# Smarttree_CMU_5_2_3.net
KiCad netlist of a schematic drawn in EAGLE
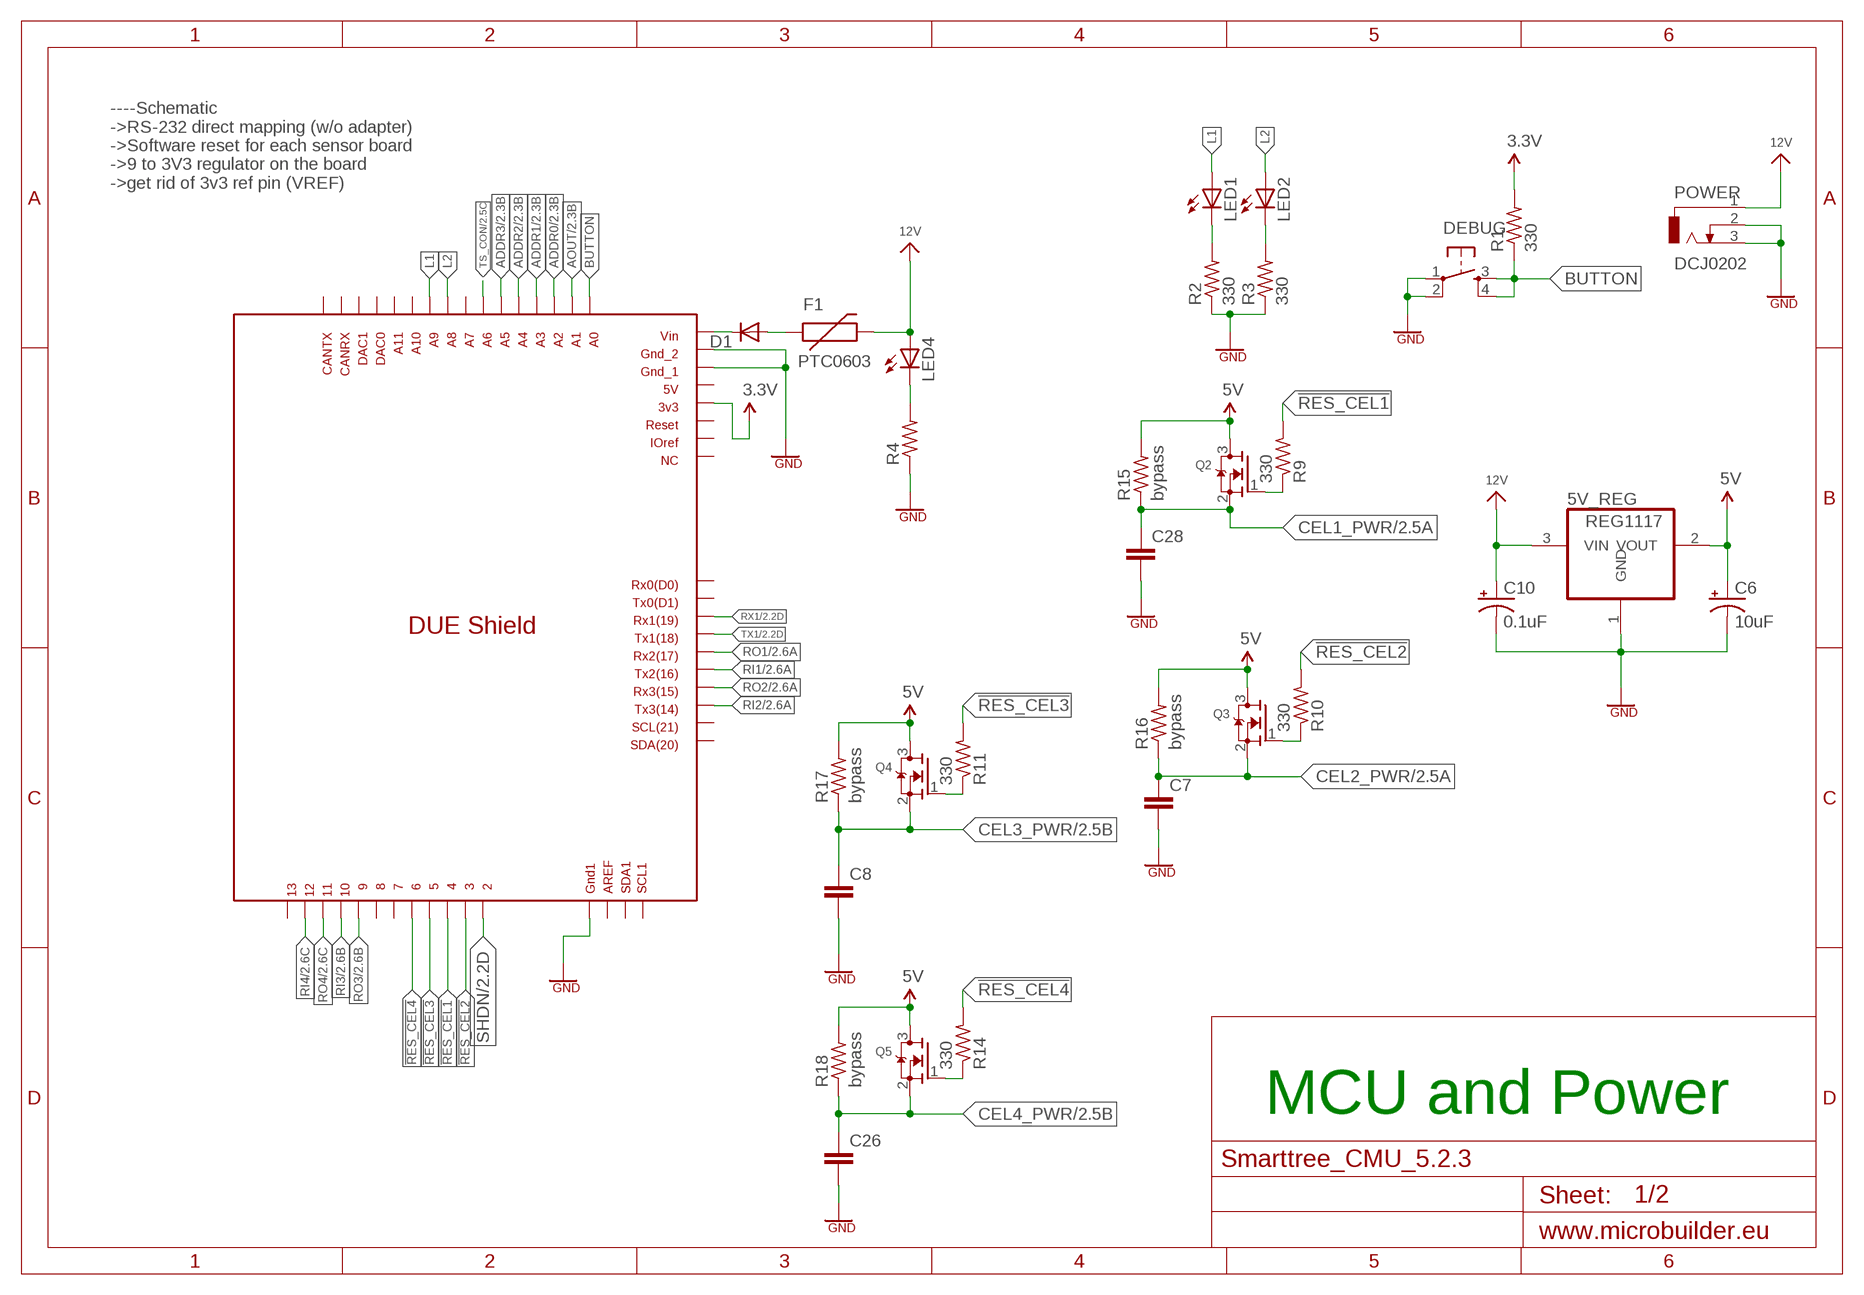
[diagram p0: schematic, sheet 1]
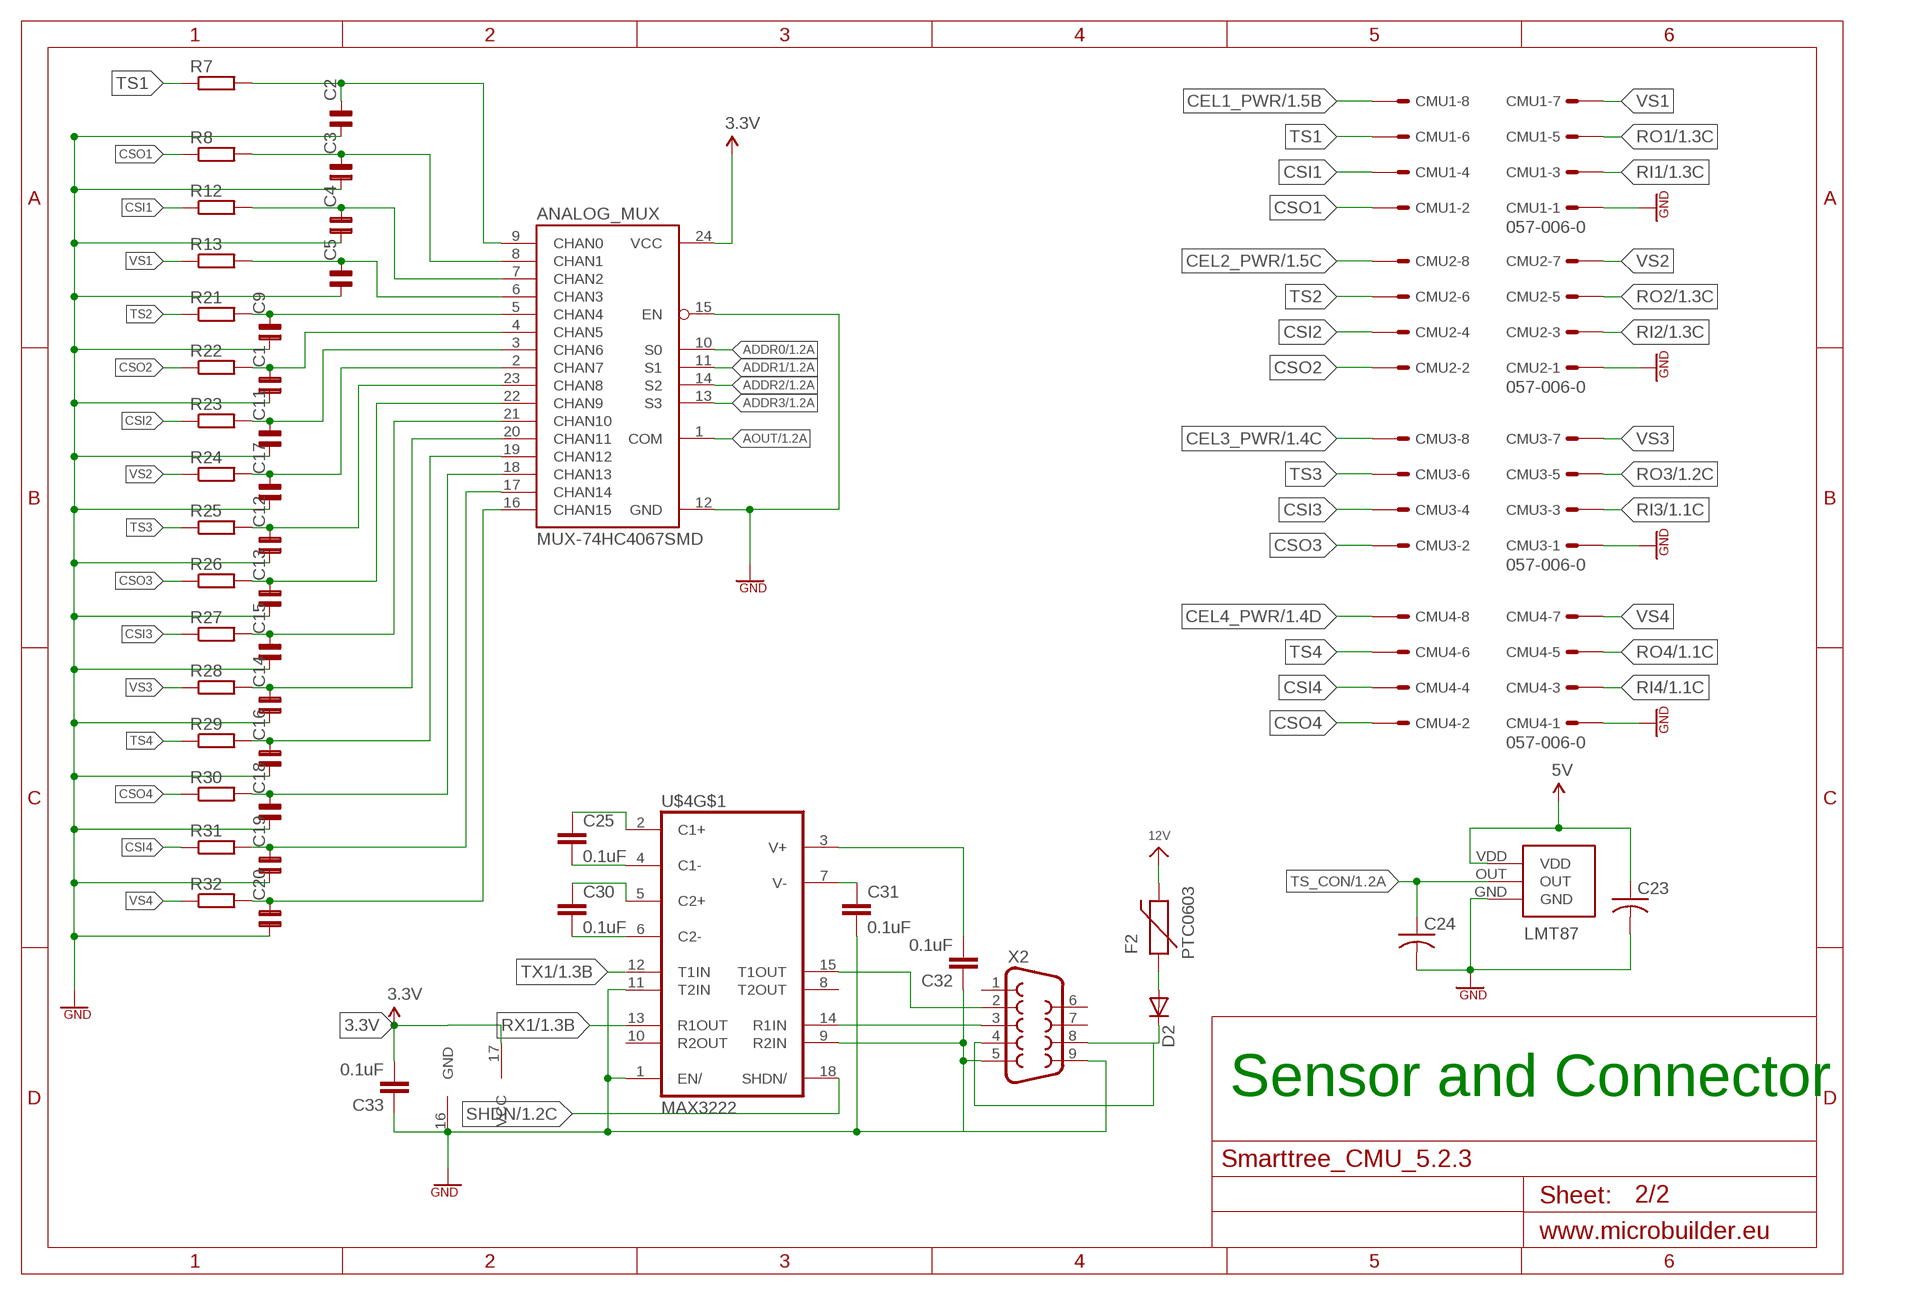
[diagram p1: schematic, sheet 2]

(export (version "E")
  (design (tool "Eeschema 10.0.6"))
  (components
    (comp (ref "ANALOG_MUX")
      (value "MUX-74HC4067SMD")
      (footprint "eagle-import:SSOP24")
      (libsource (lib "eagle-import") (part "MUX-74HC4067SMD"))
    )
    (comp (ref "C1")
      (value "C-NP-SMD-0805")
      (footprint "eagle-import:C-0805")
      (libsource (lib "eagle-import") (part "C-NP-SMD-0805"))
    )
    (comp (ref "C2")
      (value "C-NP-SMD-0805")
      (footprint "eagle-import:C-0805")
      (libsource (lib "eagle-import") (part "C-NP-SMD-0805"))
    )
    (comp (ref "C3")
      (value "C-NP-SMD-0805")
      (footprint "eagle-import:C-0805")
      (libsource (lib "eagle-import") (part "C-NP-SMD-0805"))
    )
    (comp (ref "C4")
      (value "C-NP-SMD-0805")
      (footprint "eagle-import:C-0805")
      (libsource (lib "eagle-import") (part "C-NP-SMD-0805"))
    )
    (comp (ref "C5")
      (value "C-NP-SMD-0805")
      (footprint "eagle-import:C-0805")
      (libsource (lib "eagle-import") (part "C-NP-SMD-0805"))
    )
    (comp (ref "C9")
      (value "C-NP-SMD-0805")
      (footprint "eagle-import:C-0805")
      (libsource (lib "eagle-import") (part "C-NP-SMD-0805"))
    )
    (comp (ref "C11")
      (value "C-NP-SMD-0805")
      (footprint "eagle-import:C-0805")
      (libsource (lib "eagle-import") (part "C-NP-SMD-0805"))
    )
    (comp (ref "C12")
      (value "C-NP-SMD-0805")
      (footprint "eagle-import:C-0805")
      (libsource (lib "eagle-import") (part "C-NP-SMD-0805"))
    )
    (comp (ref "C13")
      (value "C-NP-SMD-0805")
      (footprint "eagle-import:C-0805")
      (libsource (lib "eagle-import") (part "C-NP-SMD-0805"))
    )
    (comp (ref "C14")
      (value "C-NP-SMD-0805")
      (footprint "eagle-import:C-0805")
      (libsource (lib "eagle-import") (part "C-NP-SMD-0805"))
    )
    (comp (ref "C15")
      (value "C-NP-SMD-0805")
      (footprint "eagle-import:C-0805")
      (libsource (lib "eagle-import") (part "C-NP-SMD-0805"))
    )
    (comp (ref "C16")
      (value "C-NP-SMD-0805")
      (footprint "eagle-import:C-0805")
      (libsource (lib "eagle-import") (part "C-NP-SMD-0805"))
    )
    (comp (ref "C17")
      (value "C-NP-SMD-0805")
      (footprint "eagle-import:C-0805")
      (libsource (lib "eagle-import") (part "C-NP-SMD-0805"))
    )
    (comp (ref "C18")
      (value "C-NP-SMD-0805")
      (footprint "eagle-import:C-0805")
      (libsource (lib "eagle-import") (part "C-NP-SMD-0805"))
    )
    (comp (ref "C19")
      (value "C-NP-SMD-0805")
      (footprint "eagle-import:C-0805")
      (libsource (lib "eagle-import") (part "C-NP-SMD-0805"))
    )
    (comp (ref "C20")
      (value "C-NP-SMD-0805")
      (footprint "eagle-import:C-0805")
      (libsource (lib "eagle-import") (part "C-NP-SMD-0805"))
    )
    (comp (ref "C23")
      (value "C-USC0805")
      (footprint "eagle-import:C0805")
      (libsource (lib "eagle-import") (part "C-USC0805"))
    )
    (comp (ref "C24")
      (value "C-USC0805")
      (footprint "eagle-import:C0805")
      (libsource (lib "eagle-import") (part "C-USC0805"))
    )
    (comp (ref "C25")
      (value "0.1uF")
      (footprint "eagle-import:0603-CAP")
      (libsource (lib "eagle-import") (part "CAP0603-CAP"))
    )
    (comp (ref "C30")
      (value "0.1uF")
      (footprint "eagle-import:0603-CAP")
      (libsource (lib "eagle-import") (part "CAP0603-CAP"))
    )
    (comp (ref "C31")
      (value "0.1uF")
      (footprint "eagle-import:0603-CAP")
      (libsource (lib "eagle-import") (part "CAP0603-CAP"))
    )
    (comp (ref "C32")
      (value "0.1uF")
      (footprint "eagle-import:0603-CAP")
      (libsource (lib "eagle-import") (part "CAP0603-CAP"))
    )
    (comp (ref "C33")
      (value "0.1uF")
      (footprint "eagle-import:0603-CAP")
      (libsource (lib "eagle-import") (part "CAP0603-CAP"))
    )
    (comp (ref "CMU1")
      (value "057-006-0")
      (footprint "eagle-import:057-006-0")
      (libsource (lib "eagle-import") (part "057-006-0"))
    )
    (comp (ref "CMU2")
      (value "057-006-0")
      (footprint "eagle-import:057-006-0")
      (libsource (lib "eagle-import") (part "057-006-0"))
    )
    (comp (ref "CMU3")
      (value "057-006-0")
      (footprint "eagle-import:057-006-0")
      (libsource (lib "eagle-import") (part "057-006-0"))
    )
    (comp (ref "CMU4")
      (value "057-006-0")
      (footprint "eagle-import:057-006-0")
      (libsource (lib "eagle-import") (part "057-006-0"))
    )
    (comp (ref "D2")
      (value "DIODE-SOD106-R")
      (footprint "eagle-import:SOD106-R")
      (libsource (lib "eagle-import") (part "DIODE-SOD106-R"))
    )
    (comp (ref "F2")
      (value "PTC0603")
      (footprint "eagle-import:0603")
      (libsource (lib "eagle-import") (part "PTC0603"))
    )
    (comp (ref "LMT87")
      (value "LMT87_PAC")
      (footprint "eagle-import:LMT87_TO")
      (libsource (lib "eagle-import") (part "LMT87_PAC"))
    )
    (comp (ref "R7")
      (value "R-EU_R0805W")
      (footprint "eagle-import:R0805W")
      (libsource (lib "eagle-import") (part "R-EU_R0805W"))
    )
    (comp (ref "R8")
      (value "R-EU_R0805W")
      (footprint "eagle-import:R0805W")
      (libsource (lib "eagle-import") (part "R-EU_R0805W"))
    )
    (comp (ref "R12")
      (value "R-EU_R0805W")
      (footprint "eagle-import:R0805W")
      (libsource (lib "eagle-import") (part "R-EU_R0805W"))
    )
    (comp (ref "R13")
      (value "R-EU_R0805W")
      (footprint "eagle-import:R0805W")
      (libsource (lib "eagle-import") (part "R-EU_R0805W"))
    )
    (comp (ref "R21")
      (value "R-EU_R0805W")
      (footprint "eagle-import:R0805W")
      (libsource (lib "eagle-import") (part "R-EU_R0805W"))
    )
    (comp (ref "R22")
      (value "R-EU_R0805W")
      (footprint "eagle-import:R0805W")
      (libsource (lib "eagle-import") (part "R-EU_R0805W"))
    )
    (comp (ref "R23")
      (value "R-EU_R0805W")
      (footprint "eagle-import:R0805W")
      (libsource (lib "eagle-import") (part "R-EU_R0805W"))
    )
    (comp (ref "R24")
      (value "R-EU_R0805W")
      (footprint "eagle-import:R0805W")
      (libsource (lib "eagle-import") (part "R-EU_R0805W"))
    )
    (comp (ref "R25")
      (value "R-EU_R0805W")
      (footprint "eagle-import:R0805W")
      (libsource (lib "eagle-import") (part "R-EU_R0805W"))
    )
    (comp (ref "R26")
      (value "R-EU_R0805W")
      (footprint "eagle-import:R0805W")
      (libsource (lib "eagle-import") (part "R-EU_R0805W"))
    )
    (comp (ref "R27")
      (value "R-EU_R0805W")
      (footprint "eagle-import:R0805W")
      (libsource (lib "eagle-import") (part "R-EU_R0805W"))
    )
    (comp (ref "R28")
      (value "R-EU_R0805W")
      (footprint "eagle-import:R0805W")
      (libsource (lib "eagle-import") (part "R-EU_R0805W"))
    )
    (comp (ref "R29")
      (value "R-EU_R0805W")
      (footprint "eagle-import:R0805W")
      (libsource (lib "eagle-import") (part "R-EU_R0805W"))
    )
    (comp (ref "R30")
      (value "R-EU_R0805W")
      (footprint "eagle-import:R0805W")
      (libsource (lib "eagle-import") (part "R-EU_R0805W"))
    )
    (comp (ref "R31")
      (value "R-EU_R0805W")
      (footprint "eagle-import:R0805W")
      (libsource (lib "eagle-import") (part "R-EU_R0805W"))
    )
    (comp (ref "R32")
      (value "R-EU_R0805W")
      (footprint "eagle-import:R0805W")
      (libsource (lib "eagle-import") (part "R-EU_R0805W"))
    )
    (comp (ref "U$4")
      (value "MAX3222")
      (footprint "eagle-import:SO18")
      (libsource (lib "eagle-import") (part "MAX3222"))
    )
    (comp (ref "X2")
      (value "DB9MALE")
      (footprint "eagle-import:DB9_MALE")
      (libsource (lib "eagle-import") (part "DB9MALE"))
    )
    (comp (ref "5V_REG")
      (value "REG1117")
      (footprint "eagle-import:SOT223")
      (libsource (lib "eagle-import") (part "REG1117"))
    )
    (comp (ref "C6")
      (value "10uF")
      (footprint "eagle-import:EIA3216")
      (libsource (lib "eagle-import") (part "10UF-TANT"))
    )
    (comp (ref "C7")
      (value "CAP0603-CAP")
      (footprint "eagle-import:0603-CAP")
      (libsource (lib "eagle-import") (part "CAP0603-CAP"))
    )
    (comp (ref "C8")
      (value "CAP0603-CAP")
      (footprint "eagle-import:0603-CAP")
      (libsource (lib "eagle-import") (part "CAP0603-CAP"))
    )
    (comp (ref "C10")
      (value "0.1uF")
      (footprint "eagle-import:EIA3216")
      (libsource (lib "eagle-import") (part "10UF-TANT"))
    )
    (comp (ref "C26")
      (value "CAP0603-CAP")
      (footprint "eagle-import:0603-CAP")
      (libsource (lib "eagle-import") (part "CAP0603-CAP"))
    )
    (comp (ref "C28")
      (value "CAP0603-CAP")
      (footprint "eagle-import:0603-CAP")
      (libsource (lib "eagle-import") (part "CAP0603-CAP"))
    )
    (comp (ref "D1")
      (value "DIODE-SOD106-R")
      (footprint "eagle-import:SOD106-R")
      (libsource (lib "eagle-import") (part "DIODE-SOD106-R"))
    )
    (comp (ref "DEBUG")
      (value "TAC_SWITCHSMD")
      (footprint "eagle-import:TACTILE_SWITCH_SMD")
      (libsource (lib "eagle-import") (part "TAC_SWITCHSMD"))
    )
    (comp (ref "F1")
      (value "PTC0603")
      (footprint "eagle-import:0603")
      (libsource (lib "eagle-import") (part "PTC0603"))
    )
    (comp (ref "LED1")
      (value "LED-YELLOW0603")
      (footprint "eagle-import:LED-0603")
      (libsource (lib "eagle-import") (part "LED-YELLOW0603"))
    )
    (comp (ref "LED2")
      (value "LED-YELLOW0603")
      (footprint "eagle-import:LED-0603")
      (libsource (lib "eagle-import") (part "LED-YELLOW0603"))
    )
    (comp (ref "LED4")
      (value "LED-YELLOW0603")
      (footprint "eagle-import:LED-0603")
      (libsource (lib "eagle-import") (part "LED-YELLOW0603"))
    )
    (comp (ref "POWER")
      (value "DCJ0202")
      (footprint "eagle-import:DCJ0202")
      (libsource (lib "eagle-import") (part "DCJ0202"))
    )
    (comp (ref "Q2")
      (value "MOSFET-NREFLOW")
      (footprint "eagle-import:SOT23")
      (libsource (lib "eagle-import") (part "MOSFET-NREFLOW"))
    )
    (comp (ref "Q3")
      (value "MOSFET-NREFLOW")
      (footprint "eagle-import:SOT23")
      (libsource (lib "eagle-import") (part "MOSFET-NREFLOW"))
    )
    (comp (ref "Q4")
      (value "MOSFET-NREFLOW")
      (footprint "eagle-import:SOT23")
      (libsource (lib "eagle-import") (part "MOSFET-NREFLOW"))
    )
    (comp (ref "Q5")
      (value "MOSFET-NREFLOW")
      (footprint "eagle-import:SOT23")
      (libsource (lib "eagle-import") (part "MOSFET-NREFLOW"))
    )
    (comp (ref "R1")
      (value "330")
      (footprint "eagle-import:M0805")
      (libsource (lib "eagle-import") (part "R-US_M0805"))
    )
    (comp (ref "R2")
      (value "330")
      (footprint "eagle-import:M0805")
      (libsource (lib "eagle-import") (part "R-US_M0805"))
    )
    (comp (ref "R3")
      (value "330")
      (footprint "eagle-import:M0805")
      (libsource (lib "eagle-import") (part "R-US_M0805"))
    )
    (comp (ref "R4")
      (value "R-US_M0805")
      (footprint "eagle-import:M0805")
      (libsource (lib "eagle-import") (part "R-US_M0805"))
    )
    (comp (ref "R9")
      (value "330")
      (footprint "eagle-import:R0805")
      (libsource (lib "eagle-import") (part "R-US_R0805"))
    )
    (comp (ref "R10")
      (value "330")
      (footprint "eagle-import:R0805")
      (libsource (lib "eagle-import") (part "R-US_R0805"))
    )
    (comp (ref "R11")
      (value "330")
      (footprint "eagle-import:R0805")
      (libsource (lib "eagle-import") (part "R-US_R0805"))
    )
    (comp (ref "R14")
      (value "330")
      (footprint "eagle-import:R0805")
      (libsource (lib "eagle-import") (part "R-US_R0805"))
    )
    (comp (ref "R15")
      (value "bypass")
      (footprint "eagle-import:M0805")
      (libsource (lib "eagle-import") (part "R-US_M0805"))
    )
    (comp (ref "R16")
      (value "bypass")
      (footprint "eagle-import:M0805")
      (libsource (lib "eagle-import") (part "R-US_M0805"))
    )
    (comp (ref "R17")
      (value "bypass")
      (footprint "eagle-import:M0805")
      (libsource (lib "eagle-import") (part "R-US_M0805"))
    )
    (comp (ref "R18")
      (value "bypass")
      (footprint "eagle-import:M0805")
      (libsource (lib "eagle-import") (part "R-US_M0805"))
    )
    (comp (ref "U$1")
      (value "DUE(OUTLINE)")
      (footprint "eagle-import:DUE(NORMAL)")
      (libsource (lib "eagle-import") (part "DUE(OUTLINE)"))
    )
  )
  (nets
    (net (code "1") (name "3.3V") (class "Default")
      (node (ref "ANALOG_MUX") (pin "24") (pinfunction "VCC_24") (pintype "bidirectional"))
      (node (ref "C33") (pin "2") (pinfunction "2_2") (pintype "passive"))
      (node (ref "R1") (pin "2") (pinfunction "2_2") (pintype "passive"))
      (node (ref "U$1") (pin "3V3") (pinfunction "3V3_3V3") (pintype "bidirectional"))
      (node (ref "U$4") (pin "17") (pinfunction "VCC_17") (pintype "bidirectional"))
    )
    (net (code "2") (name "5V") (class "Default")
      (node (ref "5V_REG") (pin "2") (pinfunction "VOUT_2") (pintype "output"))
      (node (ref "C23") (pin "1") (pinfunction "1_1") (pintype "passive"))
      (node (ref "C6") (pin "A") (pinfunction "+_A") (pintype "passive"))
      (node (ref "LMT87") (pin "VDD") (pinfunction "VDD_VDD") (pintype "bidirectional"))
      (node (ref "Q2") (pin "3") (pinfunction "D_3") (pintype "bidirectional"))
      (node (ref "Q3") (pin "3") (pinfunction "D_3") (pintype "bidirectional"))
      (node (ref "Q4") (pin "3") (pinfunction "D_3") (pintype "bidirectional"))
      (node (ref "Q5") (pin "3") (pinfunction "D_3") (pintype "bidirectional"))
      (node (ref "R15") (pin "2") (pinfunction "2_2") (pintype "passive"))
      (node (ref "R16") (pin "2") (pinfunction "2_2") (pintype "passive"))
      (node (ref "R17") (pin "2") (pinfunction "2_2") (pintype "passive"))
      (node (ref "R18") (pin "2") (pinfunction "2_2") (pintype "passive"))
    )
    (net (code "3") (name "12V") (class "Default")
      (node (ref "5V_REG") (pin "3") (pinfunction "VIN_3") (pintype "input"))
      (node (ref "C10") (pin "A") (pinfunction "+_A") (pintype "passive"))
      (node (ref "F1") (pin "2") (pinfunction "2_2") (pintype "bidirectional"))
      (node (ref "F2") (pin "2") (pinfunction "2_2") (pintype "bidirectional"))
      (node (ref "LED4") (pin "A") (pinfunction "A_A") (pintype "passive"))
      (node (ref "POWER") (pin "1") (pinfunction "1_1") (pintype "passive"))
    )
    (net (code "4") (name "ADDR0") (class "Default")
      (node (ref "ANALOG_MUX") (pin "10") (pinfunction "S0_10") (pintype "input"))
      (node (ref "U$1") (pin "A2") (pinfunction "A2_A2") (pintype "bidirectional"))
    )
    (net (code "5") (name "ADDR1") (class "Default")
      (node (ref "ANALOG_MUX") (pin "11") (pinfunction "S1_11") (pintype "input"))
      (node (ref "U$1") (pin "A3") (pinfunction "A3_A3") (pintype "bidirectional"))
    )
    (net (code "6") (name "ADDR2") (class "Default")
      (node (ref "ANALOG_MUX") (pin "14") (pinfunction "S2_14") (pintype "input"))
      (node (ref "U$1") (pin "A4") (pinfunction "A4_A4") (pintype "bidirectional"))
    )
    (net (code "7") (name "ADDR3") (class "Default")
      (node (ref "ANALOG_MUX") (pin "13") (pinfunction "S3_13") (pintype "input"))
      (node (ref "U$1") (pin "A5") (pinfunction "A5_A5") (pintype "bidirectional"))
    )
    (net (code "8") (name "AOUT") (class "Default")
      (node (ref "ANALOG_MUX") (pin "1") (pinfunction "COM_1") (pintype "bidirectional"))
      (node (ref "U$1") (pin "A1") (pinfunction "A1_A1") (pintype "bidirectional"))
    )
    (net (code "9") (name "BUTTON") (class "Default")
      (node (ref "DEBUG") (pin "3") (pinfunction "3_3") (pintype "passive"))
      (node (ref "DEBUG") (pin "4") (pinfunction "4_4") (pintype "passive"))
      (node (ref "R1") (pin "1") (pinfunction "1_1") (pintype "passive"))
      (node (ref "U$1") (pin "A0") (pinfunction "A0_A0") (pintype "bidirectional"))
    )
    (net (code "10") (name "CEL1_PWR") (class "Default")
      (node (ref "C28") (pin "1") (pinfunction "1_1") (pintype "passive"))
      (node (ref "CMU1") (pin "7") (pinfunction "S_7") (pintype "passive"))
      (node (ref "Q2") (pin "2") (pinfunction "S_2") (pintype "bidirectional"))
      (node (ref "R15") (pin "1") (pinfunction "1_1") (pintype "passive"))
    )
    (net (code "11") (name "CEL2_PWR") (class "Default")
      (node (ref "C7") (pin "1") (pinfunction "1_1") (pintype "passive"))
      (node (ref "CMU2") (pin "7") (pinfunction "S_7") (pintype "passive"))
      (node (ref "Q3") (pin "2") (pinfunction "S_2") (pintype "bidirectional"))
      (node (ref "R16") (pin "1") (pinfunction "1_1") (pintype "passive"))
    )
    (net (code "12") (name "CEL3_PWR") (class "Default")
      (node (ref "C8") (pin "1") (pinfunction "1_1") (pintype "passive"))
      (node (ref "CMU3") (pin "7") (pinfunction "S_7") (pintype "passive"))
      (node (ref "Q4") (pin "2") (pinfunction "S_2") (pintype "bidirectional"))
      (node (ref "R17") (pin "1") (pinfunction "1_1") (pintype "passive"))
    )
    (net (code "13") (name "CEL4_PWR") (class "Default")
      (node (ref "C26") (pin "1") (pinfunction "1_1") (pintype "passive"))
      (node (ref "CMU4") (pin "7") (pinfunction "S_7") (pintype "passive"))
      (node (ref "Q5") (pin "2") (pinfunction "S_2") (pintype "bidirectional"))
      (node (ref "R18") (pin "1") (pinfunction "1_1") (pintype "passive"))
    )
    (net (code "14") (name "CSI1") (class "Default")
      (node (ref "CMU1") (pin "4") (pinfunction "S_4") (pintype "passive"))
      (node (ref "R12") (pin "1") (pinfunction "1_1") (pintype "passive"))
    )
    (net (code "15") (name "CSI2") (class "Default")
      (node (ref "CMU2") (pin "4") (pinfunction "S_4") (pintype "passive"))
      (node (ref "R23") (pin "1") (pinfunction "1_1") (pintype "passive"))
    )
    (net (code "16") (name "CSI3") (class "Default")
      (node (ref "CMU3") (pin "4") (pinfunction "S_4") (pintype "passive"))
      (node (ref "R27") (pin "1") (pinfunction "1_1") (pintype "passive"))
    )
    (net (code "17") (name "CSI4") (class "Default")
      (node (ref "CMU4") (pin "4") (pinfunction "S_4") (pintype "passive"))
      (node (ref "R31") (pin "1") (pinfunction "1_1") (pintype "passive"))
    )
    (net (code "18") (name "CSO1") (class "Default")
      (node (ref "CMU1") (pin "2") (pinfunction "S_2") (pintype "passive"))
      (node (ref "R8") (pin "1") (pinfunction "1_1") (pintype "passive"))
    )
    (net (code "19") (name "CSO2") (class "Default")
      (node (ref "CMU2") (pin "2") (pinfunction "S_2") (pintype "passive"))
      (node (ref "R22") (pin "1") (pinfunction "1_1") (pintype "passive"))
    )
    (net (code "20") (name "CSO3") (class "Default")
      (node (ref "CMU3") (pin "2") (pinfunction "S_2") (pintype "passive"))
      (node (ref "R26") (pin "1") (pinfunction "1_1") (pintype "passive"))
    )
    (net (code "21") (name "CSO4") (class "Default")
      (node (ref "CMU4") (pin "2") (pinfunction "S_2") (pintype "passive"))
      (node (ref "R30") (pin "1") (pinfunction "1_1") (pintype "passive"))
    )
    (net (code "22") (name "GND") (class "Default")
      (node (ref "5V_REG") (pin "1") (pinfunction "GND_1") (pintype "power_in"))
      (node (ref "ANALOG_MUX") (pin "12") (pinfunction "GND_12") (pintype "bidirectional"))
      (node (ref "ANALOG_MUX") (pin "15") (pinfunction "EN_15") (pintype "input"))
      (node (ref "C1") (pin "1") (pinfunction "1_1") (pintype "passive"))
      (node (ref "C10") (pin "C") (pinfunction "-_C") (pintype "passive"))
      (node (ref "C11") (pin "1") (pinfunction "1_1") (pintype "passive"))
      (node (ref "C12") (pin "1") (pinfunction "1_1") (pintype "passive"))
      (node (ref "C13") (pin "1") (pinfunction "1_1") (pintype "passive"))
      (node (ref "C14") (pin "1") (pinfunction "1_1") (pintype "passive"))
      (node (ref "C15") (pin "1") (pinfunction "1_1") (pintype "passive"))
      (node (ref "C16") (pin "1") (pinfunction "1_1") (pintype "passive"))
      (node (ref "C17") (pin "1") (pinfunction "1_1") (pintype "passive"))
      (node (ref "C18") (pin "1") (pinfunction "1_1") (pintype "passive"))
      (node (ref "C19") (pin "1") (pinfunction "1_1") (pintype "passive"))
      (node (ref "C2") (pin "1") (pinfunction "1_1") (pintype "passive"))
      (node (ref "C20") (pin "1") (pinfunction "1_1") (pintype "passive"))
      (node (ref "C23") (pin "2") (pinfunction "2_2") (pintype "passive"))
      (node (ref "C24") (pin "2") (pinfunction "2_2") (pintype "passive"))
      (node (ref "C26") (pin "2") (pinfunction "2_2") (pintype "passive"))
      (node (ref "C28") (pin "2") (pinfunction "2_2") (pintype "passive"))
      (node (ref "C3") (pin "1") (pinfunction "1_1") (pintype "passive"))
      (node (ref "C31") (pin "2") (pinfunction "2_2") (pintype "passive"))
      (node (ref "C32") (pin "1") (pinfunction "1_1") (pintype "passive"))
      (node (ref "C33") (pin "1") (pinfunction "1_1") (pintype "passive"))
      (node (ref "C4") (pin "1") (pinfunction "1_1") (pintype "passive"))
      (node (ref "C5") (pin "1") (pinfunction "1_1") (pintype "passive"))
      (node (ref "C6") (pin "C") (pinfunction "-_C") (pintype "passive"))
      (node (ref "C7") (pin "2") (pinfunction "2_2") (pintype "passive"))
      (node (ref "C8") (pin "2") (pinfunction "2_2") (pintype "passive"))
      (node (ref "C9") (pin "1") (pinfunction "1_1") (pintype "passive"))
      (node (ref "CMU1") (pin "1") (pinfunction "S_1") (pintype "passive"))
      (node (ref "CMU2") (pin "1") (pinfunction "S_1") (pintype "passive"))
      (node (ref "CMU3") (pin "1") (pinfunction "S_1") (pintype "passive"))
      (node (ref "CMU4") (pin "1") (pinfunction "S_1") (pintype "passive"))
      (node (ref "DEBUG") (pin "1") (pinfunction "1_1") (pintype "passive"))
      (node (ref "DEBUG") (pin "2") (pinfunction "2_2") (pintype "passive"))
      (node (ref "LMT87") (pin "GND") (pinfunction "GND_GND") (pintype "bidirectional"))
      (node (ref "POWER") (pin "2") (pinfunction "2_2") (pintype "passive"))
      (node (ref "POWER") (pin "3") (pinfunction "3_3") (pintype "passive"))
      (node (ref "R2") (pin "1") (pinfunction "1_1") (pintype "passive"))
      (node (ref "R3") (pin "1") (pinfunction "1_1") (pintype "passive"))
      (node (ref "R4") (pin "1") (pinfunction "1_1") (pintype "passive"))
      (node (ref "U$1") (pin "GND1") (pinfunction "GND1_GND1") (pintype "bidirectional"))
      (node (ref "U$1") (pin "GND_1") (pinfunction "GND_1_GND_1") (pintype "bidirectional"))
      (node (ref "U$1") (pin "GND_2") (pinfunction "GND_2_GND_2") (pintype "bidirectional"))
      (node (ref "U$4") (pin "1") (pinfunction "EN/_1") (pintype "input"))
      (node (ref "U$4") (pin "11") (pinfunction "T2IN_11") (pintype "input"))
      (node (ref "U$4") (pin "16") (pinfunction "GND_16") (pintype "bidirectional"))
      (node (ref "U$4") (pin "9") (pinfunction "R2IN_9") (pintype "input"))
      (node (ref "X2") (pin "5") (pinfunction "5_5") (pintype "passive"))
      (node (ref "X2") (pin "9") (pinfunction "9_9") (pintype "passive"))
    )
    (net (code "23") (name "L1") (class "Default")
      (node (ref "LED1") (pin "A") (pinfunction "A_A") (pintype "passive"))
      (node (ref "U$1") (pin "A9") (pinfunction "A9_A9") (pintype "bidirectional"))
    )
    (net (code "24") (name "L2") (class "Default")
      (node (ref "LED2") (pin "A") (pinfunction "A_A") (pintype "passive"))
      (node (ref "U$1") (pin "A8") (pinfunction "A8_A8") (pintype "bidirectional"))
    )
    (net (code "25") (name "Net-(ANALOG_MUX-CHAN0)") (class "Default")
      (node (ref "ANALOG_MUX") (pin "9") (pinfunction "CHAN0_9") (pintype "bidirectional"))
      (node (ref "C2") (pin "2") (pinfunction "2_2") (pintype "passive"))
      (node (ref "R7") (pin "2") (pinfunction "2_2") (pintype "passive"))
    )
    (net (code "26") (name "Net-(ANALOG_MUX-CHAN1)") (class "Default")
      (node (ref "ANALOG_MUX") (pin "8") (pinfunction "CHAN1_8") (pintype "bidirectional"))
      (node (ref "C3") (pin "2") (pinfunction "2_2") (pintype "passive"))
      (node (ref "R8") (pin "2") (pinfunction "2_2") (pintype "passive"))
    )
    (net (code "27") (name "Net-(ANALOG_MUX-CHAN2)") (class "Default")
      (node (ref "ANALOG_MUX") (pin "7") (pinfunction "CHAN2_7") (pintype "bidirectional"))
      (node (ref "C4") (pin "2") (pinfunction "2_2") (pintype "passive"))
      (node (ref "R12") (pin "2") (pinfunction "2_2") (pintype "passive"))
    )
    (net (code "28") (name "Net-(ANALOG_MUX-CHAN3)") (class "Default")
      (node (ref "ANALOG_MUX") (pin "6") (pinfunction "CHAN3_6") (pintype "bidirectional"))
      (node (ref "C5") (pin "2") (pinfunction "2_2") (pintype "passive"))
      (node (ref "R13") (pin "2") (pinfunction "2_2") (pintype "passive"))
    )
    (net (code "29") (name "Net-(ANALOG_MUX-CHAN4)") (class "Default")
      (node (ref "ANALOG_MUX") (pin "5") (pinfunction "CHAN4_5") (pintype "bidirectional"))
      (node (ref "C9") (pin "2") (pinfunction "2_2") (pintype "passive"))
      (node (ref "R21") (pin "2") (pinfunction "2_2") (pintype "passive"))
    )
    (net (code "30") (name "Net-(ANALOG_MUX-CHAN5)") (class "Default")
      (node (ref "ANALOG_MUX") (pin "4") (pinfunction "CHAN5_4") (pintype "bidirectional"))
      (node (ref "C1") (pin "2") (pinfunction "2_2") (pintype "passive"))
      (node (ref "R22") (pin "2") (pinfunction "2_2") (pintype "passive"))
    )
    (net (code "31") (name "Net-(ANALOG_MUX-CHAN6)") (class "Default")
      (node (ref "ANALOG_MUX") (pin "3") (pinfunction "CHAN6_3") (pintype "bidirectional"))
      (node (ref "C11") (pin "2") (pinfunction "2_2") (pintype "passive"))
      (node (ref "R23") (pin "2") (pinfunction "2_2") (pintype "passive"))
    )
    (net (code "32") (name "Net-(ANALOG_MUX-CHAN7)") (class "Default")
      (node (ref "ANALOG_MUX") (pin "2") (pinfunction "CHAN7_2") (pintype "bidirectional"))
      (node (ref "C17") (pin "2") (pinfunction "2_2") (pintype "passive"))
      (node (ref "R24") (pin "2") (pinfunction "2_2") (pintype "passive"))
    )
    (net (code "33") (name "Net-(ANALOG_MUX-CHAN8)") (class "Default")
      (node (ref "ANALOG_MUX") (pin "23") (pinfunction "CHAN8_23") (pintype "bidirectional"))
      (node (ref "C12") (pin "2") (pinfunction "2_2") (pintype "passive"))
      (node (ref "R25") (pin "2") (pinfunction "2_2") (pintype "passive"))
    )
    (net (code "34") (name "Net-(ANALOG_MUX-CHAN9)") (class "Default")
      (node (ref "ANALOG_MUX") (pin "22") (pinfunction "CHAN9_22") (pintype "bidirectional"))
      (node (ref "C13") (pin "2") (pinfunction "2_2") (pintype "passive"))
      (node (ref "R26") (pin "2") (pinfunction "2_2") (pintype "passive"))
    )
    (net (code "35") (name "Net-(ANALOG_MUX-CHAN10)") (class "Default")
      (node (ref "ANALOG_MUX") (pin "21") (pinfunction "CHAN10_21") (pintype "bidirectional"))
      (node (ref "C15") (pin "2") (pinfunction "2_2") (pintype "passive"))
      (node (ref "R27") (pin "2") (pinfunction "2_2") (pintype "passive"))
    )
    (net (code "36") (name "Net-(ANALOG_MUX-CHAN11)") (class "Default")
      (node (ref "ANALOG_MUX") (pin "20") (pinfunction "CHAN11_20") (pintype "bidirectional"))
      (node (ref "C14") (pin "2") (pinfunction "2_2") (pintype "passive"))
      (node (ref "R28") (pin "2") (pinfunction "2_2") (pintype "passive"))
    )
    (net (code "37") (name "Net-(ANALOG_MUX-CHAN12)") (class "Default")
      (node (ref "ANALOG_MUX") (pin "19") (pinfunction "CHAN12_19") (pintype "bidirectional"))
      (node (ref "C16") (pin "2") (pinfunction "2_2") (pintype "passive"))
      (node (ref "R29") (pin "2") (pinfunction "2_2") (pintype "passive"))
    )
    (net (code "38") (name "Net-(ANALOG_MUX-CHAN13)") (class "Default")
      (node (ref "ANALOG_MUX") (pin "18") (pinfunction "CHAN13_18") (pintype "bidirectional"))
      (node (ref "C18") (pin "2") (pinfunction "2_2") (pintype "passive"))
      (node (ref "R30") (pin "2") (pinfunction "2_2") (pintype "passive"))
    )
    (net (code "39") (name "Net-(ANALOG_MUX-CHAN14)") (class "Default")
      (node (ref "ANALOG_MUX") (pin "17") (pinfunction "CHAN14_17") (pintype "bidirectional"))
      (node (ref "C19") (pin "2") (pinfunction "2_2") (pintype "passive"))
      (node (ref "R31") (pin "2") (pinfunction "2_2") (pintype "passive"))
    )
    (net (code "40") (name "Net-(ANALOG_MUX-CHAN15)") (class "Default")
      (node (ref "ANALOG_MUX") (pin "16") (pinfunction "CHAN15_16") (pintype "bidirectional"))
      (node (ref "C20") (pin "2") (pinfunction "2_2") (pintype "passive"))
      (node (ref "R32") (pin "2") (pinfunction "2_2") (pintype "passive"))
    )
    (net (code "41") (name "Net-(D1-PadA)") (class "Default")
      (node (ref "D1") (pin "A") (pinfunction "A_A") (pintype "passive"))
      (node (ref "F1") (pin "1") (pinfunction "1_1") (pintype "bidirectional"))
    )
    (net (code "42") (name "Net-(D1-PadC)") (class "Default")
      (node (ref "D1") (pin "C") (pinfunction "C_C") (pintype "passive"))
      (node (ref "U$1") (pin "VIN") (pinfunction "VIN_VIN") (pintype "bidirectional"))
    )
    (net (code "43") (name "Net-(D2-PadA)") (class "Default")
      (node (ref "D2") (pin "A") (pinfunction "A_A") (pintype "passive"))
      (node (ref "F2") (pin "1") (pinfunction "1_1") (pintype "bidirectional"))
    )
    (net (code "44") (name "Net-(D2-PadC)") (class "Default")
      (node (ref "D2") (pin "C") (pinfunction "C_C") (pintype "passive"))
      (node (ref "X2") (pin "4") (pinfunction "4_4") (pintype "passive"))
      (node (ref "X2") (pin "8") (pinfunction "8_8") (pintype "passive"))
    )
    (net (code "45") (name "Net-(LED1-PadC)") (class "Default")
      (node (ref "LED1") (pin "C") (pinfunction "C_C") (pintype "passive"))
      (node (ref "R2") (pin "2") (pinfunction "2_2") (pintype "passive"))
    )
    (net (code "46") (name "Net-(LED2-PadC)") (class "Default")
      (node (ref "LED2") (pin "C") (pinfunction "C_C") (pintype "passive"))
      (node (ref "R3") (pin "2") (pinfunction "2_2") (pintype "passive"))
    )
    (net (code "47") (name "Net-(LED4-PadC)") (class "Default")
      (node (ref "LED4") (pin "C") (pinfunction "C_C") (pintype "passive"))
      (node (ref "R4") (pin "2") (pinfunction "2_2") (pintype "passive"))
    )
    (net (code "48") (name "Net-(Q2-G)") (class "Default")
      (node (ref "Q2") (pin "1") (pinfunction "G_1") (pintype "bidirectional"))
      (node (ref "R9") (pin "1") (pinfunction "1_1") (pintype "passive"))
    )
    (net (code "49") (name "Net-(Q3-G)") (class "Default")
      (node (ref "Q3") (pin "1") (pinfunction "G_1") (pintype "bidirectional"))
      (node (ref "R10") (pin "1") (pinfunction "1_1") (pintype "passive"))
    )
    (net (code "50") (name "Net-(Q4-G)") (class "Default")
      (node (ref "Q4") (pin "1") (pinfunction "G_1") (pintype "bidirectional"))
      (node (ref "R11") (pin "1") (pinfunction "1_1") (pintype "passive"))
    )
    (net (code "51") (name "Net-(Q5-G)") (class "Default")
      (node (ref "Q5") (pin "1") (pinfunction "G_1") (pintype "bidirectional"))
      (node (ref "R14") (pin "1") (pinfunction "1_1") (pintype "passive"))
    )
    (net (code "52") (name "Net-(U$4A-C1+)") (class "Default")
      (node (ref "C25") (pin "1") (pinfunction "1_1") (pintype "passive"))
      (node (ref "U$4") (pin "2") (pinfunction "C1+_2") (pintype "passive"))
    )
    (net (code "53") (name "Net-(U$4A-C1-)") (class "Default")
      (node (ref "C25") (pin "2") (pinfunction "2_2") (pintype "passive"))
      (node (ref "U$4") (pin "4") (pinfunction "C1-_4") (pintype "passive"))
    )
    (net (code "54") (name "Net-(U$4A-C2+)") (class "Default")
      (node (ref "C30") (pin "1") (pinfunction "1_1") (pintype "passive"))
      (node (ref "U$4") (pin "5") (pinfunction "C2+_5") (pintype "passive"))
    )
    (net (code "55") (name "Net-(U$4A-C2-)") (class "Default")
      (node (ref "C30") (pin "2") (pinfunction "2_2") (pintype "passive"))
      (node (ref "U$4") (pin "6") (pinfunction "C2-_6") (pintype "passive"))
    )
    (net (code "56") (name "Net-(U$4A-R1IN)") (class "Default")
      (node (ref "U$4") (pin "14") (pinfunction "R1IN_14") (pintype "input"))
      (node (ref "X2") (pin "3") (pinfunction "3_3") (pintype "passive"))
    )
    (net (code "57") (name "Net-(U$4A-T1OUT)") (class "Default")
      (node (ref "U$4") (pin "15") (pinfunction "T1OUT_15") (pintype "output"))
      (node (ref "X2") (pin "2") (pinfunction "2_2") (pintype "passive"))
    )
    (net (code "58") (name "Net-(U$4A-V+)") (class "Default")
      (node (ref "C32") (pin "2") (pinfunction "2_2") (pintype "passive"))
      (node (ref "U$4") (pin "3") (pinfunction "V+_3") (pintype "passive"))
    )
    (net (code "59") (name "Net-(U$4A-V-)") (class "Default")
      (node (ref "C31") (pin "1") (pinfunction "1_1") (pintype "passive"))
      (node (ref "U$4") (pin "7") (pinfunction "V-_7") (pintype "passive"))
    )
    (net (code "60") (name "RI1") (class "Default")
      (node (ref "CMU1") (pin "3") (pinfunction "S_3") (pintype "passive"))
      (node (ref "U$1") (pin "TX2") (pinfunction "TX2_TX2") (pintype "bidirectional"))
    )
    (net (code "61") (name "RI2") (class "Default")
      (node (ref "CMU2") (pin "3") (pinfunction "S_3") (pintype "passive"))
      (node (ref "U$1") (pin "TX3") (pinfunction "TX3_TX3") (pintype "bidirectional"))
    )
    (net (code "62") (name "RI3") (class "Default")
      (node (ref "CMU3") (pin "3") (pinfunction "S_3") (pintype "passive"))
      (node (ref "U$1") (pin "10") (pinfunction "10_10") (pintype "bidirectional"))
    )
    (net (code "63") (name "RI4") (class "Default")
      (node (ref "CMU4") (pin "3") (pinfunction "S_3") (pintype "passive"))
      (node (ref "U$1") (pin "12") (pinfunction "12_12") (pintype "bidirectional"))
    )
    (net (code "64") (name "RO1") (class "Default")
      (node (ref "CMU1") (pin "5") (pinfunction "S_5") (pintype "passive"))
      (node (ref "U$1") (pin "RX2") (pinfunction "RX2_RX2") (pintype "bidirectional"))
    )
    (net (code "65") (name "RO2") (class "Default")
      (node (ref "CMU2") (pin "5") (pinfunction "S_5") (pintype "passive"))
      (node (ref "U$1") (pin "RX3") (pinfunction "RX3_RX3") (pintype "bidirectional"))
    )
    (net (code "66") (name "RO3") (class "Default")
      (node (ref "CMU3") (pin "5") (pinfunction "S_5") (pintype "passive"))
      (node (ref "U$1") (pin "9") (pinfunction "9_9") (pintype "bidirectional"))
    )
    (net (code "67") (name "RO4") (class "Default")
      (node (ref "CMU4") (pin "5") (pinfunction "S_5") (pintype "passive"))
      (node (ref "U$1") (pin "11") (pinfunction "11_11") (pintype "bidirectional"))
    )
    (net (code "68") (name "RX1") (class "Default")
      (node (ref "U$1") (pin "RX1") (pinfunction "RX1_RX1") (pintype "bidirectional"))
      (node (ref "U$4") (pin "13") (pinfunction "R1OUT_13") (pintype "output"))
    )
    (net (code "69") (name "SHDN") (class "Default")
      (node (ref "U$1") (pin "2") (pinfunction "2_2") (pintype "bidirectional"))
      (node (ref "U$4") (pin "18") (pinfunction "SHDN/_18") (pintype "input"))
    )
    (net (code "70") (name "TS1") (class "Default")
      (node (ref "CMU1") (pin "6") (pinfunction "S_6") (pintype "passive"))
      (node (ref "R7") (pin "1") (pinfunction "1_1") (pintype "passive"))
    )
    (net (code "71") (name "TS2") (class "Default")
      (node (ref "CMU2") (pin "6") (pinfunction "S_6") (pintype "passive"))
      (node (ref "R21") (pin "1") (pinfunction "1_1") (pintype "passive"))
    )
    (net (code "72") (name "TS3") (class "Default")
      (node (ref "CMU3") (pin "6") (pinfunction "S_6") (pintype "passive"))
      (node (ref "R25") (pin "1") (pinfunction "1_1") (pintype "passive"))
    )
    (net (code "73") (name "TS4") (class "Default")
      (node (ref "CMU4") (pin "6") (pinfunction "S_6") (pintype "passive"))
      (node (ref "R29") (pin "1") (pinfunction "1_1") (pintype "passive"))
    )
    (net (code "74") (name "TS_CON") (class "Default")
      (node (ref "C24") (pin "1") (pinfunction "1_1") (pintype "passive"))
      (node (ref "LMT87") (pin "OUT") (pinfunction "OUT_OUT") (pintype "bidirectional"))
      (node (ref "U$1") (pin "A6") (pinfunction "A6_A6") (pintype "bidirectional"))
    )
    (net (code "75") (name "TX1") (class "Default")
      (node (ref "U$1") (pin "TX1") (pinfunction "TX1_TX1") (pintype "bidirectional"))
      (node (ref "U$4") (pin "12") (pinfunction "T1IN_12") (pintype "input"))
    )
    (net (code "76") (name "VS1") (class "Default")
      (node (ref "CMU1") (pin "8") (pinfunction "S_8") (pintype "passive"))
      (node (ref "R13") (pin "1") (pinfunction "1_1") (pintype "passive"))
    )
    (net (code "77") (name "VS2") (class "Default")
      (node (ref "CMU2") (pin "8") (pinfunction "S_8") (pintype "passive"))
      (node (ref "R24") (pin "1") (pinfunction "1_1") (pintype "passive"))
    )
    (net (code "78") (name "VS3") (class "Default")
      (node (ref "CMU3") (pin "8") (pinfunction "S_8") (pintype "passive"))
      (node (ref "R28") (pin "1") (pinfunction "1_1") (pintype "passive"))
    )
    (net (code "79") (name "VS4") (class "Default")
      (node (ref "CMU4") (pin "8") (pinfunction "S_8") (pintype "passive"))
      (node (ref "R32") (pin "1") (pinfunction "1_1") (pintype "passive"))
    )
    (net (code "80") (name "unconnected-(U$1-Pad5V)") (class "Default")
      (node (ref "U$1") (pin "5V") (pinfunction "5V_5V") (pintype "bidirectional"))
    )
    (net (code "81") (name "unconnected-(U$1-Pad7)") (class "Default")
      (node (ref "U$1") (pin "7") (pinfunction "7_7") (pintype "bidirectional"))
    )
    (net (code "82") (name "unconnected-(U$1-Pad8)") (class "Default")
      (node (ref "U$1") (pin "8") (pinfunction "8_8") (pintype "bidirectional"))
    )
    (net (code "83") (name "unconnected-(U$1-Pad13)") (class "Default")
      (node (ref "U$1") (pin "13") (pinfunction "13_13") (pintype "bidirectional"))
    )
    (net (code "84") (name "unconnected-(U$1-PadA7)") (class "Default")
      (node (ref "U$1") (pin "A7") (pinfunction "A7_A7") (pintype "bidirectional"))
    )
    (net (code "85") (name "unconnected-(U$1-PadA10)") (class "Default")
      (node (ref "U$1") (pin "A10") (pinfunction "A10_A10") (pintype "bidirectional"))
    )
    (net (code "86") (name "unconnected-(U$1-PadA11)") (class "Default")
      (node (ref "U$1") (pin "A11") (pinfunction "A11_A11") (pintype "bidirectional"))
    )
    (net (code "87") (name "unconnected-(U$1-PadAREF)") (class "Default")
      (node (ref "U$1") (pin "AREF") (pinfunction "AREF_AREF") (pintype "bidirectional"))
    )
    (net (code "88") (name "unconnected-(U$1-PadCANRX)") (class "Default")
      (node (ref "U$1") (pin "CANRX") (pinfunction "CANRX_CANRX") (pintype "bidirectional"))
    )
    (net (code "89") (name "unconnected-(U$1-PadCANTX)") (class "Default")
      (node (ref "U$1") (pin "CANTX") (pinfunction "CANTX_CANTX") (pintype "bidirectional"))
    )
    (net (code "90") (name "unconnected-(U$1-PadDAC0)") (class "Default")
      (node (ref "U$1") (pin "DAC0") (pinfunction "DAC0_DAC0") (pintype "bidirectional"))
    )
    (net (code "91") (name "unconnected-(U$1-PadDAC1)") (class "Default")
      (node (ref "U$1") (pin "DAC1") (pinfunction "DAC1_DAC1") (pintype "bidirectional"))
    )
    (net (code "92") (name "unconnected-(U$1-PadIOREF)") (class "Default")
      (node (ref "U$1") (pin "IOREF") (pinfunction "IOREF_IOREF") (pintype "bidirectional"))
    )
    (net (code "93") (name "unconnected-(U$1-PadNC)") (class "Default")
      (node (ref "U$1") (pin "NC") (pinfunction "NC_NC") (pintype "bidirectional"))
    )
    (net (code "94") (name "unconnected-(U$1-PadRESET)") (class "Default")
      (node (ref "U$1") (pin "RESET") (pinfunction "RESET_RESET") (pintype "bidirectional"))
    )
    (net (code "95") (name "unconnected-(U$1-PadRX0)") (class "Default")
      (node (ref "U$1") (pin "RX0") (pinfunction "RX0_RX0") (pintype "bidirectional"))
    )
    (net (code "96") (name "unconnected-(U$1-PadSCL)") (class "Default")
      (node (ref "U$1") (pin "SCL") (pinfunction "SCL_SCL") (pintype "bidirectional"))
    )
    (net (code "97") (name "unconnected-(U$1-PadSCL1)") (class "Default")
      (node (ref "U$1") (pin "SCL1") (pinfunction "SCL1_SCL1") (pintype "bidirectional"))
    )
    (net (code "98") (name "unconnected-(U$1-PadSDA)") (class "Default")
      (node (ref "U$1") (pin "SDA") (pinfunction "SDA_SDA") (pintype "bidirectional"))
    )
    (net (code "99") (name "unconnected-(U$1-PadSDA1)") (class "Default")
      (node (ref "U$1") (pin "SDA1") (pinfunction "SDA1_SDA1") (pintype "bidirectional"))
    )
    (net (code "100") (name "unconnected-(U$1-PadTX0)") (class "Default")
      (node (ref "U$1") (pin "TX0") (pinfunction "TX0_TX0") (pintype "bidirectional"))
    )
    (net (code "101") (name "unconnected-(U$4A-R2OUT-Pad10)") (class "Default")
      (node (ref "U$4") (pin "10") (pinfunction "R2OUT_10") (pintype "output"))
    )
    (net (code "102") (name "unconnected-(U$4A-T2OUT-Pad8)") (class "Default")
      (node (ref "U$4") (pin "8") (pinfunction "T2OUT_8") (pintype "output"))
    )
    (net (code "103") (name "unconnected-(X2-Pad1)") (class "Default")
      (node (ref "X2") (pin "1") (pinfunction "1_1") (pintype "passive"))
    )
    (net (code "104") (name "unconnected-(X2-Pad6)") (class "Default")
      (node (ref "X2") (pin "6") (pinfunction "6_6") (pintype "passive"))
    )
    (net (code "105") (name "unconnected-(X2-Pad7)") (class "Default")
      (node (ref "X2") (pin "7") (pinfunction "7_7") (pintype "passive"))
    )
    (net (code "106") (name "~{RES_CEL1}") (class "Default")
      (node (ref "R9") (pin "2") (pinfunction "2_2") (pintype "passive"))
      (node (ref "U$1") (pin "4") (pinfunction "4_4") (pintype "bidirectional"))
    )
    (net (code "107") (name "~{RES_CEL2}") (class "Default")
      (node (ref "R10") (pin "2") (pinfunction "2_2") (pintype "passive"))
      (node (ref "U$1") (pin "3") (pinfunction "3_3") (pintype "bidirectional"))
    )
    (net (code "108") (name "~{RES_CEL3}") (class "Default")
      (node (ref "R11") (pin "2") (pinfunction "2_2") (pintype "passive"))
      (node (ref "U$1") (pin "5") (pinfunction "5_5") (pintype "bidirectional"))
    )
    (net (code "109") (name "~{RES_CEL4}") (class "Default")
      (node (ref "R14") (pin "2") (pinfunction "2_2") (pintype "passive"))
      (node (ref "U$1") (pin "6") (pinfunction "6_6") (pintype "bidirectional"))
    )
  )
)
